# smartbedlight3.net
KiCad netlist of a schematic drawn in EAGLE
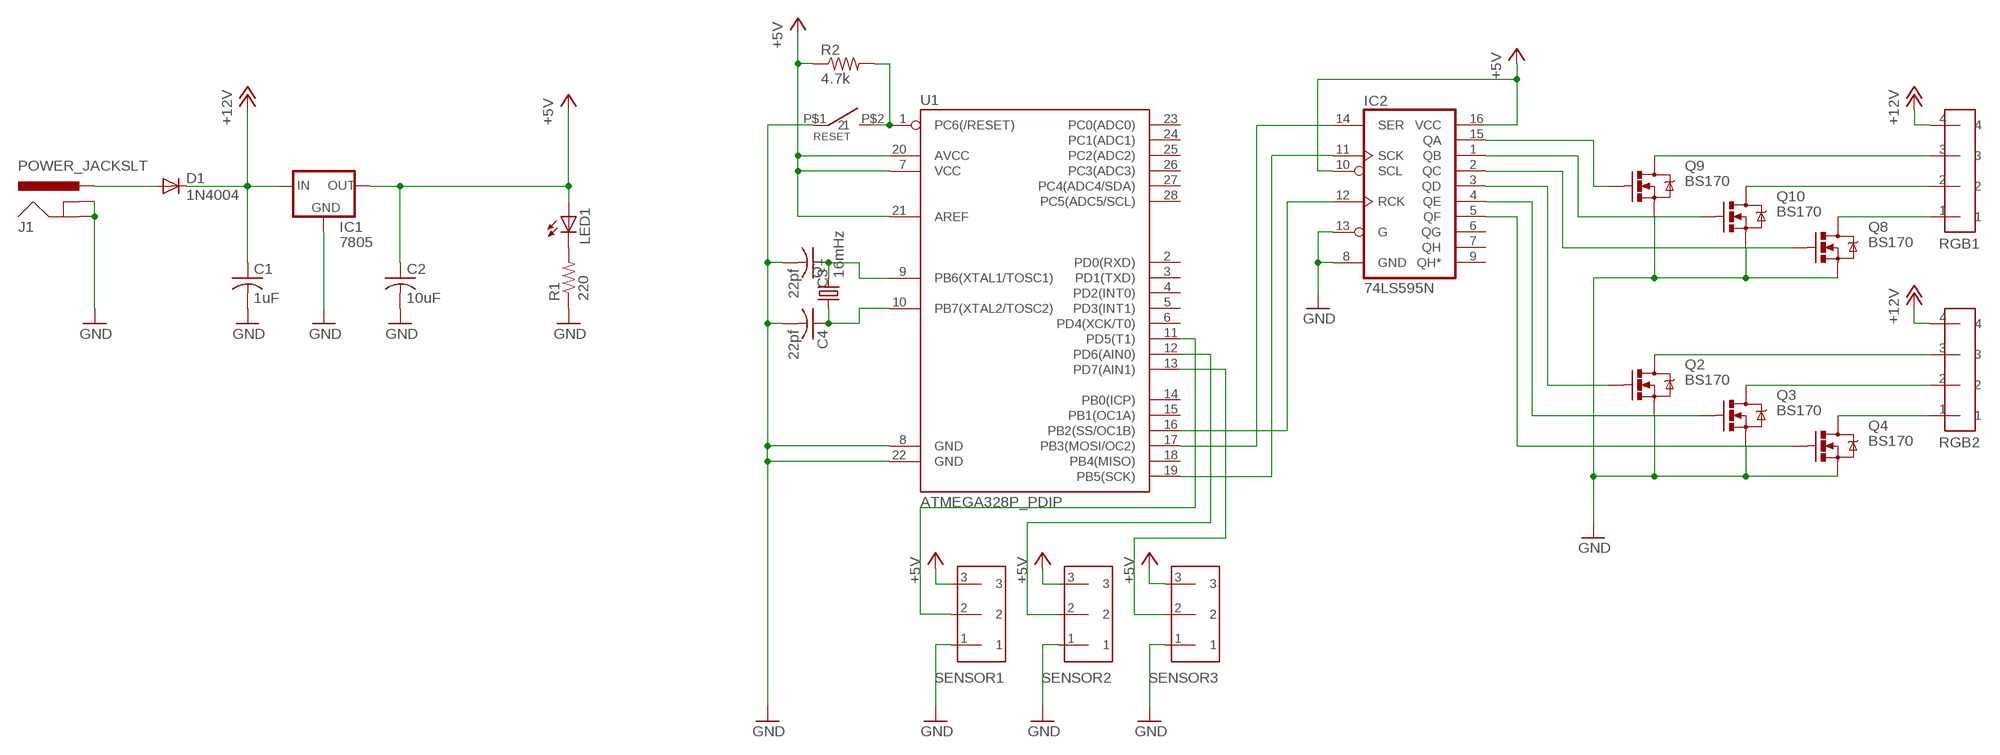
[diagram p0: schematic, sheet 1]

(export (version "E")
  (design (tool "Eeschema 10.0.6"))
  (components
    (comp (ref "C1")
      (value "1uF")
      (footprint "eagle-import:C025-030X050")
      (libsource (lib "eagle-import") (part "C-US025-030X050"))
    )
    (comp (ref "C2")
      (value "10uF")
      (footprint "eagle-import:C025-030X050")
      (libsource (lib "eagle-import") (part "C-US025-030X050"))
    )
    (comp (ref "C3")
      (value "22pf")
      (footprint "eagle-import:C025-025X050")
      (libsource (lib "eagle-import") (part "resistor_C-US025-025X050"))
    )
    (comp (ref "C4")
      (value "22pf")
      (footprint "eagle-import:C025-025X050")
      (libsource (lib "eagle-import") (part "resistor_C-US025-025X050"))
    )
    (comp (ref "D1")
      (value "1N4004")
      (footprint "eagle-import:DO41-10")
      (libsource (lib "eagle-import") (part "1N4004"))
    )
    (comp (ref "IC1")
      (value "7805")
      (footprint "eagle-import:78XXL")
      (libsource (lib "eagle-import") (part "V_REG_78XXSIDE"))
    )
    (comp (ref "IC2")
      (value "74LS595N")
      (footprint "eagle-import:DIL16")
      (libsource (lib "eagle-import") (part "74595NLS"))
    )
    (comp (ref "J1")
      (value "POWER_JACKSLT")
      (footprint "eagle-import:POWER_JACK_SLOT")
      (libsource (lib "eagle-import") (part "POWER_JACKSLT"))
    )
    (comp (ref "LED1")
      (value "LED5MM")
      (footprint "eagle-import:LED5MM")
      (libsource (lib "eagle-import") (part "LED5MM"))
    )
    (comp (ref "Q1")
      (value "16mHz")
      (footprint "eagle-import:HC49U-V")
      (libsource (lib "eagle-import") (part "CRYSTALHC49U-V"))
    )
    (comp (ref "Q2")
      (value "BS170")
      (footprint "eagle-import:TO-92")
      (libsource (lib "eagle-import") (part "MOSFET-NCHANNELBS170"))
    )
    (comp (ref "Q3")
      (value "BS170")
      (footprint "eagle-import:TO-92")
      (libsource (lib "eagle-import") (part "MOSFET-NCHANNELBS170"))
    )
    (comp (ref "Q4")
      (value "BS170")
      (footprint "eagle-import:TO-92")
      (libsource (lib "eagle-import") (part "MOSFET-NCHANNELBS170"))
    )
    (comp (ref "Q8")
      (value "BS170")
      (footprint "eagle-import:TO-92")
      (libsource (lib "eagle-import") (part "MOSFET-NCHANNELBS170"))
    )
    (comp (ref "Q9")
      (value "BS170")
      (footprint "eagle-import:TO-92")
      (libsource (lib "eagle-import") (part "MOSFET-NCHANNELBS170"))
    )
    (comp (ref "Q10")
      (value "BS170")
      (footprint "eagle-import:TO-92")
      (libsource (lib "eagle-import") (part "MOSFET-NCHANNELBS170"))
    )
    (comp (ref "R1")
      (value "220")
      (footprint "eagle-import:0204_7")
      (libsource (lib "eagle-import") (part "R-US_0204/7"))
    )
    (comp (ref "R2")
      (value "4.7k")
      (footprint "eagle-import:0207_10")
      (libsource (lib "eagle-import") (part "resistor_R-US_0207/10"))
    )
    (comp (ref "RESET")
      (value "TACK_SWITCH")
      (footprint "eagle-import:TACK_SWITCH")
      (libsource (lib "eagle-import") (part "TACK_SWITCH"))
    )
    (comp (ref "RGB1")
      (value "PINHEAD4")
      (footprint "eagle-import:PINHEAD4")
      (libsource (lib "eagle-import") (part "PINHEAD4"))
    )
    (comp (ref "RGB2")
      (value "PINHEAD4")
      (footprint "eagle-import:PINHEAD4")
      (libsource (lib "eagle-import") (part "PINHEAD4"))
    )
    (comp (ref "SENSOR1")
      (value "PINHEAD3")
      (footprint "eagle-import:PINHEAD")
      (libsource (lib "eagle-import") (part "PINHEAD3"))
    )
    (comp (ref "SENSOR2")
      (value "PINHEAD3")
      (footprint "eagle-import:PINHEAD")
      (libsource (lib "eagle-import") (part "PINHEAD3"))
    )
    (comp (ref "SENSOR3")
      (value "PINHEAD3")
      (footprint "eagle-import:PINHEAD")
      (libsource (lib "eagle-import") (part "PINHEAD3"))
    )
    (comp (ref "U1")
      (value "ATMEGA328P_PDIP")
      (footprint "eagle-import:DIL28-3")
      (libsource (lib "eagle-import") (part "ATMEGA328P_PDIP"))
    )
  )
  (nets
    (net (code "1") (name "+5V") (class "Default")
      (node (ref "C2") (pin "1") (pinfunction "1_1") (pintype "passive"))
      (node (ref "IC1") (pin "OUT") (pinfunction "OUT_OUT") (pintype "output"))
      (node (ref "IC2") (pin "10") (pinfunction "SCL_10") (pintype "input"))
      (node (ref "IC2") (pin "16") (pinfunction "VCC_16") (pintype "power_in"))
      (node (ref "LED1") (pin "A") (pinfunction "A_A") (pintype "passive"))
      (node (ref "R2") (pin "1") (pinfunction "1_1") (pintype "passive"))
      (node (ref "SENSOR1") (pin "3") (pinfunction "3_3") (pintype "bidirectional"))
      (node (ref "SENSOR2") (pin "3") (pinfunction "3_3") (pintype "bidirectional"))
      (node (ref "SENSOR3") (pin "3") (pinfunction "3_3") (pintype "bidirectional"))
      (node (ref "U1") (pin "20") (pinfunction "AVCC_20") (pintype "bidirectional"))
      (node (ref "U1") (pin "21") (pinfunction "AREF_21") (pintype "bidirectional"))
      (node (ref "U1") (pin "7") (pinfunction "VCC_7") (pintype "bidirectional"))
    )
    (net (code "2") (name "+12V") (class "Default")
      (node (ref "C1") (pin "1") (pinfunction "1_1") (pintype "passive"))
      (node (ref "D1") (pin "C") (pinfunction "C_C") (pintype "passive"))
      (node (ref "IC1") (pin "IN") (pinfunction "IN_IN") (pintype "input"))
      (node (ref "RGB1") (pin "4") (pinfunction "4_4") (pintype "bidirectional"))
      (node (ref "RGB2") (pin "4") (pinfunction "4_4") (pintype "bidirectional"))
    )
    (net (code "3") (name "GND") (class "Default")
      (node (ref "C1") (pin "2") (pinfunction "2_2") (pintype "passive"))
      (node (ref "C2") (pin "2") (pinfunction "2_2") (pintype "passive"))
      (node (ref "C3") (pin "2") (pinfunction "2_2") (pintype "passive"))
      (node (ref "C4") (pin "2") (pinfunction "2_2") (pintype "passive"))
      (node (ref "IC1") (pin "GND") (pinfunction "GND_GND") (pintype "input"))
      (node (ref "IC2") (pin "13") (pinfunction "G_13") (pintype "input"))
      (node (ref "IC2") (pin "8") (pinfunction "GND_8") (pintype "power_in"))
      (node (ref "J1") (pin "GND@1") (pinfunction "GNDBREAK_GND@1") (pintype "bidirectional"))
      (node (ref "J1") (pin "GND@2") (pinfunction "GND_GND@2") (pintype "bidirectional"))
      (node (ref "Q10") (pin "3") (pinfunction "S_3") (pintype "passive"))
      (node (ref "Q2") (pin "3") (pinfunction "S_3") (pintype "passive"))
      (node (ref "Q3") (pin "3") (pinfunction "S_3") (pintype "passive"))
      (node (ref "Q4") (pin "3") (pinfunction "S_3") (pintype "passive"))
      (node (ref "Q8") (pin "3") (pinfunction "S_3") (pintype "passive"))
      (node (ref "Q9") (pin "3") (pinfunction "S_3") (pintype "passive"))
      (node (ref "R1") (pin "1") (pinfunction "1_1") (pintype "passive"))
      (node (ref "RESET") (pin "P$1") (pinfunction "1_P$1") (pintype "bidirectional"))
      (node (ref "SENSOR1") (pin "1") (pinfunction "1_1") (pintype "bidirectional"))
      (node (ref "SENSOR2") (pin "1") (pinfunction "1_1") (pintype "bidirectional"))
      (node (ref "SENSOR3") (pin "1") (pinfunction "1_1") (pintype "bidirectional"))
      (node (ref "U1") (pin "22") (pinfunction "GND_22") (pintype "bidirectional"))
      (node (ref "U1") (pin "8") (pinfunction "GND_8") (pintype "bidirectional"))
    )
    (net (code "4") (name "Net-(D1-PadA)") (class "Default")
      (node (ref "D1") (pin "A") (pinfunction "A_A") (pintype "passive"))
      (node (ref "J1") (pin "PWR") (pinfunction "PWR_PWR") (pintype "bidirectional"))
    )
    (net (code "5") (name "Net-(IC2-QA)") (class "Default")
      (node (ref "IC2") (pin "15") (pinfunction "QA_15") (pintype "tri_state"))
      (node (ref "Q9") (pin "2") (pinfunction "G_2") (pintype "passive"))
    )
    (net (code "6") (name "Net-(IC2-QB)") (class "Default")
      (node (ref "IC2") (pin "1") (pinfunction "QB_1") (pintype "tri_state"))
      (node (ref "Q10") (pin "2") (pinfunction "G_2") (pintype "passive"))
    )
    (net (code "7") (name "Net-(IC2-QC)") (class "Default")
      (node (ref "IC2") (pin "2") (pinfunction "QC_2") (pintype "tri_state"))
      (node (ref "Q8") (pin "2") (pinfunction "G_2") (pintype "passive"))
    )
    (net (code "8") (name "Net-(IC2-QD)") (class "Default")
      (node (ref "IC2") (pin "3") (pinfunction "QD_3") (pintype "tri_state"))
      (node (ref "Q2") (pin "2") (pinfunction "G_2") (pintype "passive"))
    )
    (net (code "9") (name "Net-(IC2-QE)") (class "Default")
      (node (ref "IC2") (pin "4") (pinfunction "QE_4") (pintype "tri_state"))
      (node (ref "Q3") (pin "2") (pinfunction "G_2") (pintype "passive"))
    )
    (net (code "10") (name "Net-(IC2-QF)") (class "Default")
      (node (ref "IC2") (pin "5") (pinfunction "QF_5") (pintype "tri_state"))
      (node (ref "Q4") (pin "2") (pinfunction "G_2") (pintype "passive"))
    )
    (net (code "11") (name "Net-(IC2-RCK)") (class "Default")
      (node (ref "IC2") (pin "12") (pinfunction "RCK_12") (pintype "input"))
      (node (ref "U1") (pin "16") (pinfunction "PB2(SS/OC1B)_16") (pintype "bidirectional"))
    )
    (net (code "12") (name "Net-(IC2-SCK)") (class "Default")
      (node (ref "IC2") (pin "11") (pinfunction "SCK_11") (pintype "input"))
      (node (ref "U1") (pin "19") (pinfunction "PB5(SCK)_19") (pintype "bidirectional"))
    )
    (net (code "13") (name "Net-(IC2-SER)") (class "Default")
      (node (ref "IC2") (pin "14") (pinfunction "SER_14") (pintype "input"))
      (node (ref "U1") (pin "17") (pinfunction "PB3(MOSI/OC2)_17") (pintype "bidirectional"))
    )
    (net (code "14") (name "Net-(LED1-C)") (class "Default")
      (node (ref "LED1") (pin "K") (pinfunction "C_K") (pintype "passive"))
      (node (ref "R1") (pin "2") (pinfunction "2_2") (pintype "passive"))
    )
    (net (code "15") (name "Net-(Q2-D)") (class "Default")
      (node (ref "Q2") (pin "1") (pinfunction "D_1") (pintype "passive"))
      (node (ref "RGB2") (pin "3") (pinfunction "3_3") (pintype "bidirectional"))
    )
    (net (code "16") (name "Net-(Q3-D)") (class "Default")
      (node (ref "Q3") (pin "1") (pinfunction "D_1") (pintype "passive"))
      (node (ref "RGB2") (pin "2") (pinfunction "2_2") (pintype "bidirectional"))
    )
    (net (code "17") (name "Net-(Q4-D)") (class "Default")
      (node (ref "Q4") (pin "1") (pinfunction "D_1") (pintype "passive"))
      (node (ref "RGB2") (pin "1") (pinfunction "1_1") (pintype "bidirectional"))
    )
    (net (code "18") (name "Net-(Q8-D)") (class "Default")
      (node (ref "Q8") (pin "1") (pinfunction "D_1") (pintype "passive"))
      (node (ref "RGB1") (pin "1") (pinfunction "1_1") (pintype "bidirectional"))
    )
    (net (code "19") (name "Net-(Q9-D)") (class "Default")
      (node (ref "Q9") (pin "1") (pinfunction "D_1") (pintype "passive"))
      (node (ref "RGB1") (pin "3") (pinfunction "3_3") (pintype "bidirectional"))
    )
    (net (code "20") (name "Net-(Q10-D)") (class "Default")
      (node (ref "Q10") (pin "1") (pinfunction "D_1") (pintype "passive"))
      (node (ref "RGB1") (pin "2") (pinfunction "2_2") (pintype "bidirectional"))
    )
    (net (code "21") (name "Net-(RESET-2)") (class "Default")
      (node (ref "R2") (pin "2") (pinfunction "2_2") (pintype "passive"))
      (node (ref "RESET") (pin "P$2") (pinfunction "2_P$2") (pintype "bidirectional"))
      (node (ref "U1") (pin "1") (pinfunction "PC6(/RESET)_1") (pintype "bidirectional"))
    )
    (net (code "22") (name "Net-(U1-PB6(XTAL1{slash}TOSC1))") (class "Default")
      (node (ref "C3") (pin "1") (pinfunction "1_1") (pintype "passive"))
      (node (ref "Q1") (pin "2") (pinfunction "2_2") (pintype "passive"))
      (node (ref "U1") (pin "9") (pinfunction "PB6(XTAL1/TOSC1)_9") (pintype "bidirectional"))
    )
    (net (code "23") (name "Net-(U1-PB7(XTAL2{slash}TOSC2))") (class "Default")
      (node (ref "C4") (pin "1") (pinfunction "1_1") (pintype "passive"))
      (node (ref "Q1") (pin "1") (pinfunction "1_1") (pintype "passive"))
      (node (ref "U1") (pin "10") (pinfunction "PB7(XTAL2/TOSC2)_10") (pintype "bidirectional"))
    )
    (net (code "24") (name "Net-(U1-PD5(T1))") (class "Default")
      (node (ref "SENSOR1") (pin "2") (pinfunction "2_2") (pintype "bidirectional"))
      (node (ref "U1") (pin "11") (pinfunction "PD5(T1)_11") (pintype "bidirectional"))
    )
    (net (code "25") (name "Net-(U1-PD6(AIN0))") (class "Default")
      (node (ref "SENSOR2") (pin "2") (pinfunction "2_2") (pintype "bidirectional"))
      (node (ref "U1") (pin "12") (pinfunction "PD6(AIN0)_12") (pintype "bidirectional"))
    )
    (net (code "26") (name "Net-(U1-PD7(AIN1))") (class "Default")
      (node (ref "SENSOR3") (pin "2") (pinfunction "2_2") (pintype "bidirectional"))
      (node (ref "U1") (pin "13") (pinfunction "PD7(AIN1)_13") (pintype "bidirectional"))
    )
    (net (code "27") (name "unconnected-(IC2-QG-Pad6)") (class "Default")
      (node (ref "IC2") (pin "6") (pinfunction "QG_6") (pintype "tri_state"))
    )
    (net (code "28") (name "unconnected-(IC2-QH*-Pad9)") (class "Default")
      (node (ref "IC2") (pin "9") (pinfunction "QH*_9") (pintype "tri_state"))
    )
    (net (code "29") (name "unconnected-(IC2-QH-Pad7)") (class "Default")
      (node (ref "IC2") (pin "7") (pinfunction "QH_7") (pintype "tri_state"))
    )
    (net (code "30") (name "unconnected-(U1-PB0(ICP)-Pad14)") (class "Default")
      (node (ref "U1") (pin "14") (pinfunction "PB0(ICP)_14") (pintype "bidirectional"))
    )
    (net (code "31") (name "unconnected-(U1-PB1(OC1A)-Pad15)") (class "Default")
      (node (ref "U1") (pin "15") (pinfunction "PB1(OC1A)_15") (pintype "bidirectional"))
    )
    (net (code "32") (name "unconnected-(U1-PB4(MISO)-Pad18)") (class "Default")
      (node (ref "U1") (pin "18") (pinfunction "PB4(MISO)_18") (pintype "bidirectional"))
    )
    (net (code "33") (name "unconnected-(U1-PC0(ADC0)-Pad23)") (class "Default")
      (node (ref "U1") (pin "23") (pinfunction "PC0(ADC0)_23") (pintype "bidirectional"))
    )
    (net (code "34") (name "unconnected-(U1-PC1(ADC1)-Pad24)") (class "Default")
      (node (ref "U1") (pin "24") (pinfunction "PC1(ADC1)_24") (pintype "bidirectional"))
    )
    (net (code "35") (name "unconnected-(U1-PC2(ADC2)-Pad25)") (class "Default")
      (node (ref "U1") (pin "25") (pinfunction "PC2(ADC2)_25") (pintype "bidirectional"))
    )
    (net (code "36") (name "unconnected-(U1-PC3(ADC3)-Pad26)") (class "Default")
      (node (ref "U1") (pin "26") (pinfunction "PC3(ADC3)_26") (pintype "bidirectional"))
    )
    (net (code "37") (name "unconnected-(U1-PC4(ADC4{slash}SDA)-Pad27)") (class "Default")
      (node (ref "U1") (pin "27") (pinfunction "PC4(ADC4/SDA)_27") (pintype "bidirectional"))
    )
    (net (code "38") (name "unconnected-(U1-PC5(ADC5{slash}SCL)-Pad28)") (class "Default")
      (node (ref "U1") (pin "28") (pinfunction "PC5(ADC5/SCL)_28") (pintype "bidirectional"))
    )
    (net (code "39") (name "unconnected-(U1-PD0(RXD)-Pad2)") (class "Default")
      (node (ref "U1") (pin "2") (pinfunction "PD0(RXD)_2") (pintype "bidirectional"))
    )
    (net (code "40") (name "unconnected-(U1-PD1(TXD)-Pad3)") (class "Default")
      (node (ref "U1") (pin "3") (pinfunction "PD1(TXD)_3") (pintype "bidirectional"))
    )
    (net (code "41") (name "unconnected-(U1-PD2(INT0)-Pad4)") (class "Default")
      (node (ref "U1") (pin "4") (pinfunction "PD2(INT0)_4") (pintype "bidirectional"))
    )
    (net (code "42") (name "unconnected-(U1-PD3(INT1)-Pad5)") (class "Default")
      (node (ref "U1") (pin "5") (pinfunction "PD3(INT1)_5") (pintype "bidirectional"))
    )
    (net (code "43") (name "unconnected-(U1-PD4(XCK{slash}T0)-Pad6)") (class "Default")
      (node (ref "U1") (pin "6") (pinfunction "PD4(XCK/T0)_6") (pintype "bidirectional"))
    )
  )
)
